# FDDplus3.net
KiCad netlist of a schematic drawn in Altium Designer
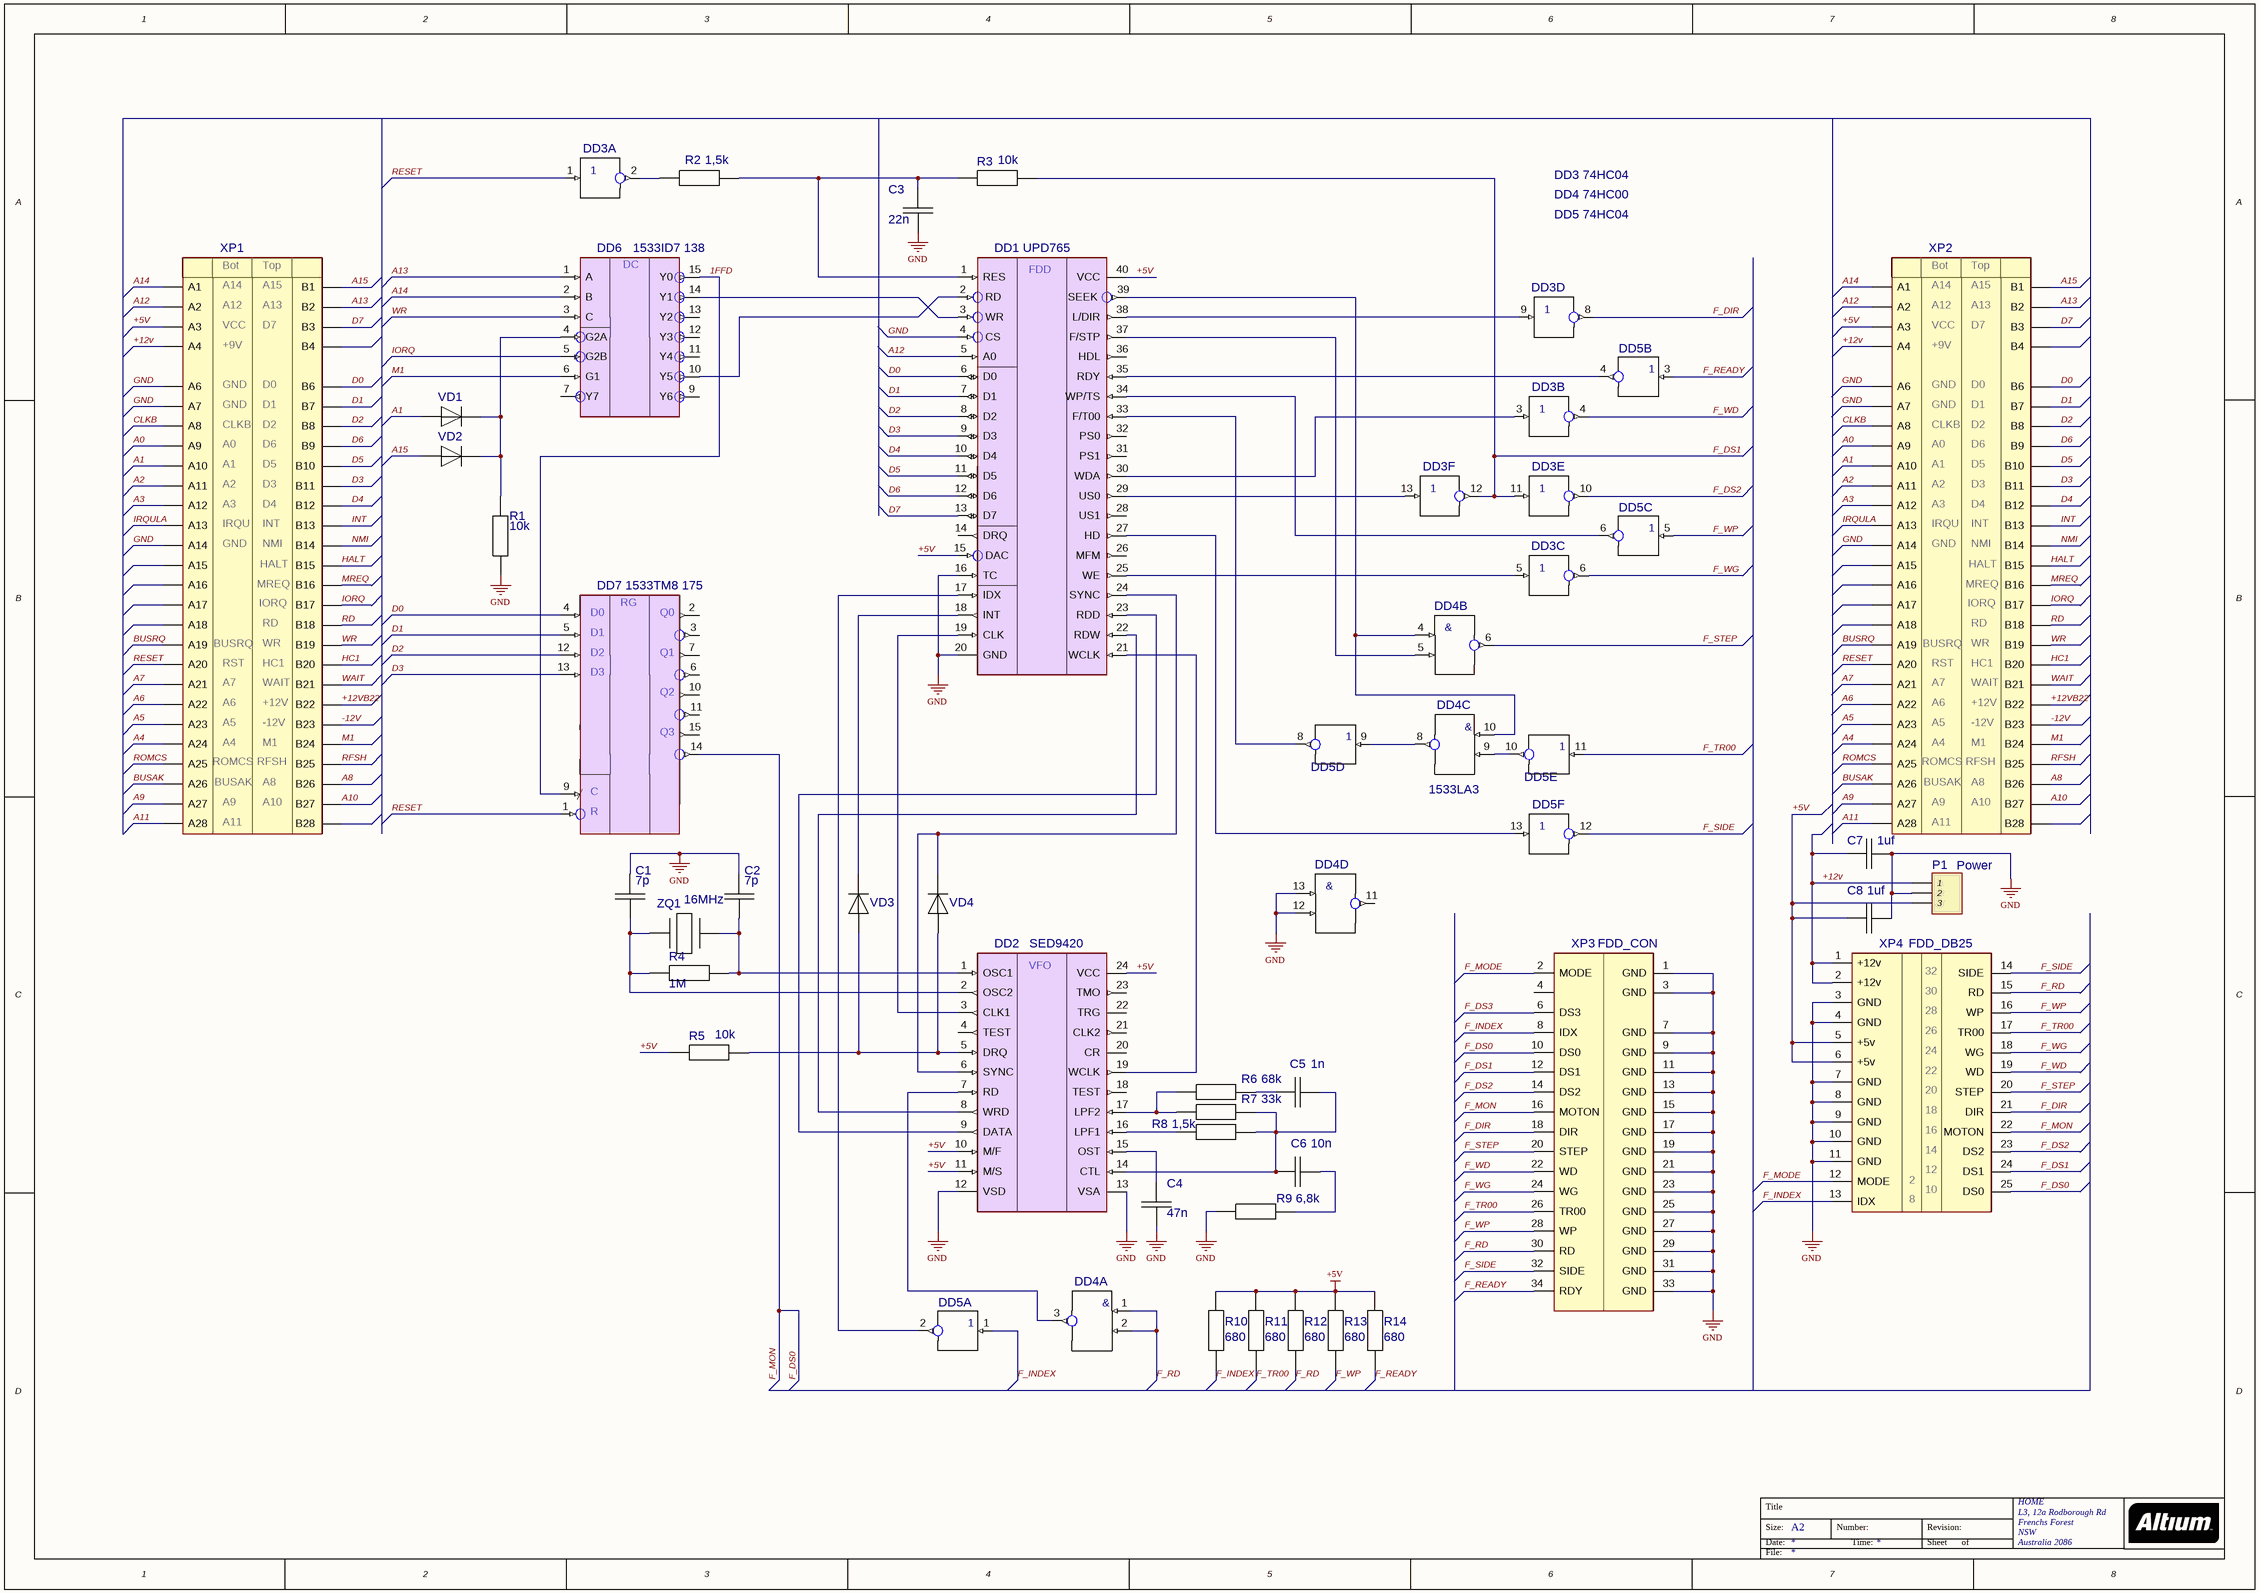
[diagram p0: FDDplus3.SchDoc]

(export (version "E")
  (design (tool "Eeschema 10.0.6"))
  (components
    (comp (ref "C1")
      (value "7p")
      (footprint "K10-17_75")
      (fields (field (name "Comment") "K10-17_75"))
      (libsource (lib "Pentagon") (part "K10-17_75"))
    )
    (comp (ref "C2")
      (value "7p")
      (footprint "K10-17_75")
      (fields (field (name "Comment") "K10-17_75"))
      (libsource (lib "Pentagon") (part "K10-17_75"))
    )
    (comp (ref "C3")
      (value "22n")
      (footprint "K10-17_75")
      (fields (field (name "Comment") "K10-17_75"))
      (libsource (lib "Pentagon") (part "K10-17_75"))
    )
    (comp (ref "C4")
      (value "47n")
      (footprint "K10-17_75")
      (fields (field (name "Comment") "K10-17_75"))
      (libsource (lib "Pentagon") (part "K10-17_75"))
    )
    (comp (ref "C5")
      (value "1n")
      (footprint "K10-17_75")
      (fields (field (name "Comment") "K10-17_75"))
      (libsource (lib "Pentagon") (part "K10-17_75"))
    )
    (comp (ref "C6")
      (value "10n")
      (footprint "K10-17_75")
      (fields (field (name "Comment") "K10-17_75"))
      (libsource (lib "Pentagon") (part "K10-17_75"))
    )
    (comp (ref "C7")
      (value "1uf")
      (footprint "K10-17_75")
      (fields (field (name "Comment") "K10-17_75"))
      (libsource (lib "Pentagon") (part "K10-17_75"))
    )
    (comp (ref "C8")
      (value "1uf")
      (footprint "K10-17_75")
      (fields (field (name "Comment") "K10-17_75"))
      (libsource (lib "Pentagon") (part "K10-17_75"))
    )
    (comp (ref "DD1") (value "UPD765") (footprint "DIP40_15") (libsource (lib "Pentagon") (part "UPD765")))
    (comp (ref "DD2") (value "SED9420") (footprint "DIP24_15") (libsource (lib "Pentagon") (part "SED9420")))
    (comp (ref "DD3") (value "1533LN1") (footprint "DIP14") (libsource (lib "") (part "1533LN1_2")))
    (comp (ref "DD4") (value "1533LA3") (footprint "DIP14") (libsource (lib "Pentagon") (part "1533LA3")))
    (comp (ref "DD5") (value "1533LN1") (footprint "DIP14") (libsource (lib "") (part "1533LN1_1")))
    (comp (ref "DD6") (value "1533ID7 138") (footprint "DIP16") (libsource (lib "Pentagon") (part "1533ID7")))
    (comp (ref "DD7") (value "1533TM8 175") (footprint "DIP16") (libsource (lib "Pentagon") (part "1533TM8")))
    (comp (ref "P1")
      (value "Power")
      (footprint "HDR1X3")
      (description "Header, 3-Pin")
      (fields (field (name "PUBLISHER") "Altium Limited"))
      (libsource (lib "Miscellaneous Connectors") (part "Header 3"))
    )
    (comp (ref "R1")
      (value "10k")
      (footprint "R0125-2_5")
      (fields (field (name "Comment") "R0125-2_5"))
      (libsource (lib "Pentagon") (part "R0125-2_5"))
    )
    (comp (ref "R2")
      (value "1,5k")
      (footprint "R0125-2_5")
      (fields (field (name "Comment") "R0125-2_5"))
      (libsource (lib "Pentagon") (part "R0125-2_5"))
    )
    (comp (ref "R3")
      (value "10k")
      (footprint "R0125-2_5")
      (fields (field (name "Comment") "R0125-2_5"))
      (libsource (lib "Pentagon") (part "R0125-2_5"))
    )
    (comp (ref "R4")
      (value "1M")
      (footprint "R0125-2_5")
      (fields (field (name "Comment") "R0125-2_5"))
      (libsource (lib "Pentagon") (part "R0125-2_5"))
    )
    (comp (ref "R5")
      (value "10k")
      (footprint "R0125-2_5")
      (fields (field (name "Comment") "R0125-2_5"))
      (libsource (lib "Pentagon") (part "R0125-2_5"))
    )
    (comp (ref "R6")
      (value "68k")
      (footprint "R0125-2_5")
      (fields (field (name "Comment") "R0125-2_5"))
      (libsource (lib "Pentagon") (part "R0125-2_5"))
    )
    (comp (ref "R7")
      (value "33k")
      (footprint "R0125-2_5")
      (fields (field (name "Comment") "R0125-2_5"))
      (libsource (lib "Pentagon") (part "R0125-2_5"))
    )
    (comp (ref "R8")
      (value "1,5k")
      (footprint "R0125-2_5")
      (fields (field (name "Comment") "R0125-2_5"))
      (libsource (lib "Pentagon") (part "R0125-2_5"))
    )
    (comp (ref "R9")
      (value "6,8k")
      (footprint "R0125-2_5")
      (fields (field (name "Comment") "R0125-2_5"))
      (libsource (lib "Pentagon") (part "R0125-2_5"))
    )
    (comp (ref "R10")
      (value "680")
      (footprint "R0125-2_5")
      (fields (field (name "Comment") "R0125-2_5"))
      (libsource (lib "Pentagon") (part "R0125-2_5"))
    )
    (comp (ref "R11")
      (value "680")
      (footprint "R0125-2_5")
      (fields (field (name "Comment") "R0125-2_5"))
      (libsource (lib "Pentagon") (part "R0125-2_5"))
    )
    (comp (ref "R12")
      (value "680")
      (footprint "R0125-2_5")
      (fields (field (name "Comment") "R0125-2_5"))
      (libsource (lib "Pentagon") (part "R0125-2_5"))
    )
    (comp (ref "R13")
      (value "680")
      (footprint "R0125-2_5")
      (fields (field (name "Comment") "R0125-2_5"))
      (libsource (lib "Pentagon") (part "R0125-2_5"))
    )
    (comp (ref "R14")
      (value "680")
      (footprint "R0125-2_5")
      (fields (field (name "Comment") "R0125-2_5"))
      (libsource (lib "Pentagon") (part "R0125-2_5"))
    )
    (comp (ref "VD1")
      (value "KD522-2_5")
      (footprint "KD522-2_5")
      (libsource (lib "Pentagon") (part "KD522-2_5"))
    )
    (comp (ref "VD2")
      (value "KD522-2_5")
      (footprint "KD522-2_5")
      (libsource (lib "Pentagon") (part "KD522-2_5"))
    )
    (comp (ref "VD3")
      (value "KD522-2_5")
      (footprint "KD522-2_5")
      (libsource (lib "Pentagon") (part "KD522-2_5"))
    )
    (comp (ref "VD4")
      (value "KD522-2_5")
      (footprint "KD522-2_5")
      (libsource (lib "Pentagon") (part "KD522-2_5"))
    )
    (comp (ref "XP1") (value "ZX EDGE") (footprint "ZX_EDGE") (libsource (lib "Pentagon") (part "ZX EDGE")))
    (comp (ref "XP2") (value "ZX EDGE") (footprint "ZX_EDGE") (libsource (lib "Pentagon") (part "ZX EDGE")))
    (comp (ref "XP3")
      (value "FDD_CON")
      (footprint "FDD_CON_Male")
      (libsource (lib "Pentagon") (part "FDD_CON"))
    )
    (comp (ref "XP4")
      (value "FDD_DB25")
      (footprint "DSUB1.385-2H25A")
      (libsource (lib "Pentagon") (part "FDD_DB25"))
    )
    (comp (ref "ZQ1")
      (value "16MHz")
      (footprint "RK169MD")
      (fields (field (name "Comment") "RK169MD"))
      (libsource (lib "Pentagon") (part "RK169MD"))
    )
  )
  (nets
    (net (code "1") (name "+5V") (class "Default")
      (node (ref "C8") (pin "2") (pinfunction "B_2") (pintype "passive"))
      (node (ref "DD1") (pin "15") (pinfunction "DAC_15") (pintype "input"))
      (node (ref "DD1") (pin "40") (pinfunction "VCC_40") (pintype "power_in"))
      (node (ref "DD2") (pin "10") (pinfunction "M/F_10") (pintype "input"))
      (node (ref "DD2") (pin "11") (pinfunction "M/S_11") (pintype "input"))
      (node (ref "DD2") (pin "24") (pinfunction "VCC_24") (pintype "power_in"))
      (node (ref "DD3") (pin "14") (pinfunction "+5V_14") (pintype "power_in"))
      (node (ref "DD4") (pin "14") (pinfunction "+5V_14") (pintype "power_in"))
      (node (ref "DD5") (pin "14") (pinfunction "+5V_14") (pintype "power_in"))
      (node (ref "DD6") (pin "16") (pinfunction "+5V_16") (pintype "power_in"))
      (node (ref "DD7") (pin "16") (pinfunction "+5V_16") (pintype "power_in"))
      (node (ref "P1") (pin "3") (pinfunction "3_3") (pintype "passive"))
      (node (ref "R10") (pin "1") (pinfunction "A_1") (pintype "passive"))
      (node (ref "R11") (pin "1") (pinfunction "A_1") (pintype "passive"))
      (node (ref "R12") (pin "1") (pinfunction "A_1") (pintype "passive"))
      (node (ref "R13") (pin "1") (pinfunction "A_1") (pintype "passive"))
      (node (ref "R14") (pin "1") (pinfunction "A_1") (pintype "passive"))
      (node (ref "R5") (pin "2") (pinfunction "B_2") (pintype "passive"))
      (node (ref "XP1") (pin "3") (pinfunction "A3_3") (pintype "power_in"))
      (node (ref "XP2") (pin "3") (pinfunction "A3_3") (pintype "power_in"))
      (node (ref "XP4") (pin "5") (pinfunction "+5v_5") (pintype "passive"))
      (node (ref "XP4") (pin "6") (pinfunction "+5v_6") (pintype "passive"))
    )
    (net (code "2") (name "/+12VB22") (class "Default")
      (node (ref "XP1") (pin "50") (pinfunction "B22_50") (pintype "passive"))
      (node (ref "XP2") (pin "50") (pinfunction "B22_50") (pintype "passive"))
    )
    (net (code "3") (name "/+12v") (class "Default")
      (node (ref "C7") (pin "2") (pinfunction "B_2") (pintype "passive"))
      (node (ref "P1") (pin "1") (pinfunction "1_1") (pintype "passive"))
      (node (ref "XP1") (pin "4") (pinfunction "A4_4") (pintype "passive"))
      (node (ref "XP2") (pin "4") (pinfunction "A4_4") (pintype "passive"))
      (node (ref "XP4") (pin "1") (pinfunction "+12v_1") (pintype "passive"))
      (node (ref "XP4") (pin "2") (pinfunction "+12v_2") (pintype "passive"))
    )
    (net (code "4") (name "/-12V") (class "Default")
      (node (ref "XP1") (pin "51") (pinfunction "B23_51") (pintype "passive"))
      (node (ref "XP2") (pin "51") (pinfunction "B23_51") (pintype "passive"))
    )
    (net (code "5") (name "/1FFD") (class "Default")
      (node (ref "DD6") (pin "15") (pinfunction "Y0_15") (pintype "output"))
      (node (ref "DD7") (pin "9") (pinfunction "C_9") (pintype "input"))
    )
    (net (code "6") (name "/A0") (class "Default")
      (node (ref "XP1") (pin "9") (pinfunction "A9_9") (pintype "passive"))
      (node (ref "XP2") (pin "9") (pinfunction "A9_9") (pintype "passive"))
    )
    (net (code "7") (name "/A1") (class "Default")
      (node (ref "VD1") (pin "1") (pinfunction "A_1") (pintype "passive"))
      (node (ref "XP1") (pin "10") (pinfunction "A10_10") (pintype "passive"))
      (node (ref "XP2") (pin "10") (pinfunction "A10_10") (pintype "passive"))
    )
    (net (code "8") (name "/A2") (class "Default")
      (node (ref "XP1") (pin "11") (pinfunction "A11_11") (pintype "passive"))
      (node (ref "XP2") (pin "11") (pinfunction "A11_11") (pintype "passive"))
    )
    (net (code "9") (name "/A3") (class "Default")
      (node (ref "XP1") (pin "12") (pinfunction "A12_12") (pintype "passive"))
      (node (ref "XP2") (pin "12") (pinfunction "A12_12") (pintype "passive"))
    )
    (net (code "10") (name "/A4") (class "Default")
      (node (ref "XP1") (pin "24") (pinfunction "A24_24") (pintype "passive"))
      (node (ref "XP2") (pin "24") (pinfunction "A24_24") (pintype "passive"))
    )
    (net (code "11") (name "/A5") (class "Default")
      (node (ref "XP1") (pin "23") (pinfunction "A23_23") (pintype "passive"))
      (node (ref "XP2") (pin "23") (pinfunction "A23_23") (pintype "passive"))
    )
    (net (code "12") (name "/A6") (class "Default")
      (node (ref "XP1") (pin "22") (pinfunction "A22_22") (pintype "passive"))
      (node (ref "XP2") (pin "22") (pinfunction "A22_22") (pintype "passive"))
    )
    (net (code "13") (name "/A7") (class "Default")
      (node (ref "XP1") (pin "21") (pinfunction "A21_21") (pintype "passive"))
      (node (ref "XP2") (pin "21") (pinfunction "A21_21") (pintype "passive"))
    )
    (net (code "14") (name "/A8") (class "Default")
      (node (ref "XP1") (pin "54") (pinfunction "B26_54") (pintype "passive"))
      (node (ref "XP2") (pin "54") (pinfunction "B26_54") (pintype "passive"))
    )
    (net (code "15") (name "/A9") (class "Default")
      (node (ref "XP1") (pin "27") (pinfunction "A27_27") (pintype "passive"))
      (node (ref "XP2") (pin "27") (pinfunction "A27_27") (pintype "passive"))
    )
    (net (code "16") (name "/A10") (class "Default")
      (node (ref "XP1") (pin "55") (pinfunction "B27_55") (pintype "passive"))
      (node (ref "XP2") (pin "55") (pinfunction "B27_55") (pintype "passive"))
    )
    (net (code "17") (name "/A11") (class "Default")
      (node (ref "XP1") (pin "28") (pinfunction "A28_28") (pintype "passive"))
      (node (ref "XP2") (pin "28") (pinfunction "A28_28") (pintype "passive"))
    )
    (net (code "18") (name "/A12") (class "Default")
      (node (ref "DD1") (pin "5") (pinfunction "A0_5") (pintype "input"))
      (node (ref "XP1") (pin "2") (pinfunction "A2_2") (pintype "passive"))
      (node (ref "XP2") (pin "2") (pinfunction "A2_2") (pintype "passive"))
    )
    (net (code "19") (name "/A13") (class "Default")
      (node (ref "DD6") (pin "1") (pinfunction "A_1") (pintype "input"))
      (node (ref "XP1") (pin "30") (pinfunction "B2_30") (pintype "passive"))
      (node (ref "XP2") (pin "30") (pinfunction "B2_30") (pintype "passive"))
    )
    (net (code "20") (name "/A14") (class "Default")
      (node (ref "DD6") (pin "2") (pinfunction "B_2") (pintype "input"))
      (node (ref "XP1") (pin "1") (pinfunction "A1_1") (pintype "passive"))
      (node (ref "XP2") (pin "1") (pinfunction "A1_1") (pintype "passive"))
    )
    (net (code "21") (name "/A15") (class "Default")
      (node (ref "VD2") (pin "1") (pinfunction "A_1") (pintype "passive"))
      (node (ref "XP1") (pin "29") (pinfunction "B1_29") (pintype "passive"))
      (node (ref "XP2") (pin "29") (pinfunction "B1_29") (pintype "passive"))
    )
    (net (code "22") (name "/BUSAK") (class "Default")
      (node (ref "XP1") (pin "26") (pinfunction "A26_26") (pintype "passive"))
      (node (ref "XP2") (pin "26") (pinfunction "A26_26") (pintype "passive"))
    )
    (net (code "23") (name "/BUSRQ") (class "Default")
      (node (ref "XP1") (pin "19") (pinfunction "A19_19") (pintype "passive"))
      (node (ref "XP2") (pin "19") (pinfunction "A19_19") (pintype "passive"))
    )
    (net (code "24") (name "/CLKB") (class "Default")
      (node (ref "XP1") (pin "8") (pinfunction "A8_8") (pintype "passive"))
      (node (ref "XP2") (pin "8") (pinfunction "A8_8") (pintype "passive"))
    )
    (net (code "25") (name "/D0") (class "Default")
      (node (ref "DD1") (pin "6") (pinfunction "D0_6") (pintype "bidirectional"))
      (node (ref "DD7") (pin "4") (pinfunction "D0_4") (pintype "input"))
      (node (ref "XP1") (pin "34") (pinfunction "B6_34") (pintype "passive"))
      (node (ref "XP2") (pin "34") (pinfunction "B6_34") (pintype "passive"))
    )
    (net (code "26") (name "/D1") (class "Default")
      (node (ref "DD1") (pin "7") (pinfunction "D1_7") (pintype "bidirectional"))
      (node (ref "DD7") (pin "5") (pinfunction "D1_5") (pintype "input"))
      (node (ref "XP1") (pin "35") (pinfunction "B7_35") (pintype "passive"))
      (node (ref "XP2") (pin "35") (pinfunction "B7_35") (pintype "passive"))
    )
    (net (code "27") (name "/D2") (class "Default")
      (node (ref "DD1") (pin "8") (pinfunction "D2_8") (pintype "bidirectional"))
      (node (ref "DD7") (pin "12") (pinfunction "D2_12") (pintype "input"))
      (node (ref "XP1") (pin "36") (pinfunction "B8_36") (pintype "passive"))
      (node (ref "XP2") (pin "36") (pinfunction "B8_36") (pintype "passive"))
    )
    (net (code "28") (name "/D3") (class "Default")
      (node (ref "DD1") (pin "9") (pinfunction "D3_9") (pintype "bidirectional"))
      (node (ref "DD7") (pin "13") (pinfunction "D3_13") (pintype "input"))
      (node (ref "XP1") (pin "39") (pinfunction "B11_39") (pintype "passive"))
      (node (ref "XP2") (pin "39") (pinfunction "B11_39") (pintype "passive"))
    )
    (net (code "29") (name "/D4") (class "Default")
      (node (ref "DD1") (pin "10") (pinfunction "D4_10") (pintype "bidirectional"))
      (node (ref "XP1") (pin "40") (pinfunction "B12_40") (pintype "passive"))
      (node (ref "XP2") (pin "40") (pinfunction "B12_40") (pintype "passive"))
    )
    (net (code "30") (name "/D5") (class "Default")
      (node (ref "DD1") (pin "11") (pinfunction "D5_11") (pintype "bidirectional"))
      (node (ref "XP1") (pin "38") (pinfunction "B10_38") (pintype "passive"))
      (node (ref "XP2") (pin "38") (pinfunction "B10_38") (pintype "passive"))
    )
    (net (code "31") (name "/D6") (class "Default")
      (node (ref "DD1") (pin "12") (pinfunction "D6_12") (pintype "bidirectional"))
      (node (ref "XP1") (pin "37") (pinfunction "B9_37") (pintype "passive"))
      (node (ref "XP2") (pin "37") (pinfunction "B9_37") (pintype "passive"))
    )
    (net (code "32") (name "/D7") (class "Default")
      (node (ref "DD1") (pin "13") (pinfunction "D7_13") (pintype "bidirectional"))
      (node (ref "XP1") (pin "31") (pinfunction "B3_31") (pintype "passive"))
      (node (ref "XP2") (pin "31") (pinfunction "B3_31") (pintype "passive"))
    )
    (net (code "33") (name "/F_DIR") (class "Default")
      (node (ref "DD3") (pin "8") (pinfunction "B_8") (pintype "output"))
      (node (ref "XP3") (pin "18") (pinfunction "DIR_18") (pintype "passive"))
      (node (ref "XP4") (pin "21") (pinfunction "DIR_21") (pintype "passive"))
    )
    (net (code "34") (name "/F_DS0") (class "Default")
      (node (ref "DD7") (pin "14") (pinfunction "Q4/_14") (pintype "output"))
      (node (ref "XP3") (pin "10") (pinfunction "DS0_10") (pintype "passive"))
      (node (ref "XP3") (pin "16") (pinfunction "MOTON_16") (pintype "passive"))
      (node (ref "XP4") (pin "22") (pinfunction "MOTON_22") (pintype "passive"))
      (node (ref "XP4") (pin "25") (pinfunction "DS0_25") (pintype "passive"))
    )
    (net (code "35") (name "/F_DS1") (class "Default")
      (node (ref "DD3") (pin "11") (pinfunction "A_11") (pintype "input"))
      (node (ref "DD3") (pin "12") (pinfunction "B_12") (pintype "output"))
      (node (ref "R3") (pin "1") (pinfunction "A_1") (pintype "passive"))
      (node (ref "XP3") (pin "12") (pinfunction "DS1_12") (pintype "passive"))
      (node (ref "XP4") (pin "24") (pinfunction "DS1_24") (pintype "passive"))
    )
    (net (code "36") (name "/F_DS2") (class "Default")
      (node (ref "DD3") (pin "10") (pinfunction "B_10") (pintype "output"))
      (node (ref "XP3") (pin "14") (pinfunction "DS2_14") (pintype "passive"))
      (node (ref "XP4") (pin "23") (pinfunction "DS2_23") (pintype "passive"))
    )
    (net (code "37") (name "/F_DS3") (class "Default")
      (node (ref "XP3") (pin "6") (pinfunction "DS3_6") (pintype "passive"))
    )
    (net (code "38") (name "/F_INDEX") (class "Default")
      (node (ref "DD5") (pin "1") (pinfunction "A_1") (pintype "input"))
      (node (ref "R10") (pin "2") (pinfunction "B_2") (pintype "passive"))
      (node (ref "XP3") (pin "8") (pinfunction "IDX_8") (pintype "passive"))
      (node (ref "XP4") (pin "13") (pinfunction "IDX_13") (pintype "passive"))
    )
    (net (code "39") (name "/F_MODE") (class "Default")
      (node (ref "XP3") (pin "2") (pinfunction "MODE_2") (pintype "passive"))
      (node (ref "XP4") (pin "12") (pinfunction "MODE_12") (pintype "passive"))
    )
    (net (code "40") (name "/F_RD") (class "Default")
      (node (ref "DD4") (pin "1") (pinfunction "A_1") (pintype "input"))
      (node (ref "DD4") (pin "2") (pinfunction "B_2") (pintype "input"))
      (node (ref "R12") (pin "2") (pinfunction "B_2") (pintype "passive"))
      (node (ref "XP3") (pin "30") (pinfunction "RD_30") (pintype "passive"))
      (node (ref "XP4") (pin "15") (pinfunction "RD_15") (pintype "passive"))
    )
    (net (code "41") (name "/F_READY") (class "Default")
      (node (ref "DD5") (pin "3") (pinfunction "A_3") (pintype "input"))
      (node (ref "R14") (pin "2") (pinfunction "B_2") (pintype "passive"))
      (node (ref "XP3") (pin "34") (pinfunction "RDY_34") (pintype "passive"))
    )
    (net (code "42") (name "/F_SIDE") (class "Default")
      (node (ref "DD5") (pin "12") (pinfunction "B_12") (pintype "output"))
      (node (ref "XP3") (pin "32") (pinfunction "SIDE_32") (pintype "passive"))
      (node (ref "XP4") (pin "14") (pinfunction "SIDE_14") (pintype "passive"))
    )
    (net (code "43") (name "/F_STEP") (class "Default")
      (node (ref "DD4") (pin "6") (pinfunction "C_6") (pintype "output"))
      (node (ref "XP3") (pin "20") (pinfunction "STEP_20") (pintype "passive"))
      (node (ref "XP4") (pin "20") (pinfunction "STEP_20") (pintype "passive"))
    )
    (net (code "44") (name "/F_TR00") (class "Default")
      (node (ref "DD5") (pin "11") (pinfunction "A_11") (pintype "input"))
      (node (ref "R11") (pin "2") (pinfunction "B_2") (pintype "passive"))
      (node (ref "XP3") (pin "26") (pinfunction "TR00_26") (pintype "passive"))
      (node (ref "XP4") (pin "17") (pinfunction "TR00_17") (pintype "passive"))
    )
    (net (code "45") (name "/F_WD") (class "Default")
      (node (ref "DD3") (pin "4") (pinfunction "B_4") (pintype "output"))
      (node (ref "XP3") (pin "22") (pinfunction "WD_22") (pintype "passive"))
      (node (ref "XP4") (pin "19") (pinfunction "WD_19") (pintype "passive"))
    )
    (net (code "46") (name "/F_WG") (class "Default")
      (node (ref "DD3") (pin "6") (pinfunction "B_6") (pintype "output"))
      (node (ref "XP3") (pin "24") (pinfunction "WG_24") (pintype "passive"))
      (node (ref "XP4") (pin "18") (pinfunction "WG_18") (pintype "passive"))
    )
    (net (code "47") (name "/F_WP") (class "Default")
      (node (ref "DD5") (pin "5") (pinfunction "A_5") (pintype "input"))
      (node (ref "R13") (pin "2") (pinfunction "B_2") (pintype "passive"))
      (node (ref "XP3") (pin "28") (pinfunction "WP_28") (pintype "passive"))
      (node (ref "XP4") (pin "16") (pinfunction "WP_16") (pintype "passive"))
    )
    (net (code "48") (name "/HALT") (class "Default")
      (node (ref "XP1") (pin "43") (pinfunction "B15_43") (pintype "passive"))
      (node (ref "XP2") (pin "43") (pinfunction "B15_43") (pintype "passive"))
    )
    (net (code "49") (name "/HC1") (class "Default")
      (node (ref "XP1") (pin "48") (pinfunction "B20_48") (pintype "passive"))
      (node (ref "XP2") (pin "48") (pinfunction "B20_48") (pintype "passive"))
    )
    (net (code "50") (name "/INT") (class "Default")
      (node (ref "XP1") (pin "41") (pinfunction "B13_41") (pintype "passive"))
      (node (ref "XP2") (pin "41") (pinfunction "B13_41") (pintype "passive"))
    )
    (net (code "51") (name "/IORQ") (class "Default")
      (node (ref "DD6") (pin "5") (pinfunction "G2B_5") (pintype "input"))
      (node (ref "XP1") (pin "45") (pinfunction "B17_45") (pintype "passive"))
      (node (ref "XP2") (pin "45") (pinfunction "B17_45") (pintype "passive"))
    )
    (net (code "52") (name "/IRQULA") (class "Default")
      (node (ref "XP1") (pin "13") (pinfunction "A13_13") (pintype "passive"))
      (node (ref "XP2") (pin "13") (pinfunction "A13_13") (pintype "passive"))
    )
    (net (code "53") (name "/M1") (class "Default")
      (node (ref "DD6") (pin "6") (pinfunction "G1_6") (pintype "input"))
      (node (ref "XP1") (pin "52") (pinfunction "B24_52") (pintype "passive"))
      (node (ref "XP2") (pin "52") (pinfunction "B24_52") (pintype "passive"))
    )
    (net (code "54") (name "/MREQ") (class "Default")
      (node (ref "XP1") (pin "44") (pinfunction "B16_44") (pintype "passive"))
      (node (ref "XP2") (pin "44") (pinfunction "B16_44") (pintype "passive"))
    )
    (net (code "55") (name "/NMI") (class "Default")
      (node (ref "XP1") (pin "42") (pinfunction "B14_42") (pintype "passive"))
      (node (ref "XP2") (pin "42") (pinfunction "B14_42") (pintype "passive"))
    )
    (net (code "56") (name "/RD") (class "Default")
      (node (ref "XP1") (pin "46") (pinfunction "B18_46") (pintype "passive"))
      (node (ref "XP2") (pin "46") (pinfunction "B18_46") (pintype "passive"))
    )
    (net (code "57") (name "/RESET") (class "Default")
      (node (ref "DD3") (pin "1") (pinfunction "A_1") (pintype "input"))
      (node (ref "DD7") (pin "1") (pinfunction "R_1") (pintype "input"))
      (node (ref "XP1") (pin "20") (pinfunction "A20_20") (pintype "passive"))
      (node (ref "XP2") (pin "20") (pinfunction "A20_20") (pintype "passive"))
    )
    (net (code "58") (name "/RFSH") (class "Default")
      (node (ref "XP1") (pin "53") (pinfunction "B25_53") (pintype "passive"))
      (node (ref "XP2") (pin "53") (pinfunction "B25_53") (pintype "passive"))
    )
    (net (code "59") (name "/ROMCS") (class "Default")
      (node (ref "XP1") (pin "25") (pinfunction "A25_25") (pintype "passive"))
      (node (ref "XP2") (pin "25") (pinfunction "A25_25") (pintype "passive"))
    )
    (net (code "60") (name "/WAIT") (class "Default")
      (node (ref "XP1") (pin "49") (pinfunction "B21_49") (pintype "passive"))
      (node (ref "XP2") (pin "49") (pinfunction "B21_49") (pintype "passive"))
    )
    (net (code "61") (name "/WR") (class "Default")
      (node (ref "DD6") (pin "3") (pinfunction "C_3") (pintype "input"))
      (node (ref "XP1") (pin "47") (pinfunction "B19_47") (pintype "passive"))
      (node (ref "XP2") (pin "47") (pinfunction "B19_47") (pintype "passive"))
    )
    (net (code "62") (name "GND") (class "Default")
      (node (ref "C1") (pin "2") (pinfunction "B_2") (pintype "passive"))
      (node (ref "C2") (pin "2") (pinfunction "B_2") (pintype "passive"))
      (node (ref "C3") (pin "1") (pinfunction "A_1") (pintype "passive"))
      (node (ref "C4") (pin "1") (pinfunction "A_1") (pintype "passive"))
      (node (ref "C7") (pin "1") (pinfunction "A_1") (pintype "passive"))
      (node (ref "C8") (pin "1") (pinfunction "A_1") (pintype "passive"))
      (node (ref "DD1") (pin "16") (pinfunction "TC_16") (pintype "input"))
      (node (ref "DD1") (pin "20") (pinfunction "GND_20") (pintype "power_in"))
      (node (ref "DD1") (pin "4") (pinfunction "CS_4") (pintype "input"))
      (node (ref "DD2") (pin "12") (pinfunction "VSD_12") (pintype "power_in"))
      (node (ref "DD2") (pin "13") (pinfunction "VSA_13") (pintype "power_in"))
      (node (ref "DD3") (pin "7") (pinfunction "GND_7") (pintype "power_in"))
      (node (ref "DD4") (pin "12") (pinfunction "B_12") (pintype "input"))
      (node (ref "DD4") (pin "13") (pinfunction "A_13") (pintype "input"))
      (node (ref "DD4") (pin "7") (pinfunction "GND_7") (pintype "power_in"))
      (node (ref "DD5") (pin "7") (pinfunction "GND_7") (pintype "power_in"))
      (node (ref "DD6") (pin "8") (pinfunction "GND_8") (pintype "power_in"))
      (node (ref "DD7") (pin "8") (pinfunction "GND_8") (pintype "power_in"))
      (node (ref "P1") (pin "2") (pinfunction "2_2") (pintype "passive"))
      (node (ref "R1") (pin "1") (pinfunction "A_1") (pintype "passive"))
      (node (ref "R9") (pin "2") (pinfunction "B_2") (pintype "passive"))
      (node (ref "XP1") (pin "14") (pinfunction "A14_14") (pintype "power_in"))
      (node (ref "XP1") (pin "6") (pinfunction "A6_6") (pintype "power_in"))
      (node (ref "XP1") (pin "7") (pinfunction "A7_7") (pintype "power_in"))
      (node (ref "XP2") (pin "14") (pinfunction "A14_14") (pintype "power_in"))
      (node (ref "XP2") (pin "6") (pinfunction "A6_6") (pintype "power_in"))
      (node (ref "XP2") (pin "7") (pinfunction "A7_7") (pintype "power_in"))
      (node (ref "XP3") (pin "1") (pinfunction "GND_1") (pintype "passive"))
      (node (ref "XP3") (pin "11") (pinfunction "GND_11") (pintype "passive"))
      (node (ref "XP3") (pin "13") (pinfunction "GND_13") (pintype "passive"))
      (node (ref "XP3") (pin "15") (pinfunction "GND_15") (pintype "passive"))
      (node (ref "XP3") (pin "17") (pinfunction "GND_17") (pintype "passive"))
      (node (ref "XP3") (pin "19") (pinfunction "GND_19") (pintype "passive"))
      (node (ref "XP3") (pin "21") (pinfunction "GND_21") (pintype "passive"))
      (node (ref "XP3") (pin "23") (pinfunction "GND_23") (pintype "passive"))
      (node (ref "XP3") (pin "25") (pinfunction "GND_25") (pintype "passive"))
      (node (ref "XP3") (pin "27") (pinfunction "GND_27") (pintype "passive"))
      (node (ref "XP3") (pin "29") (pinfunction "GND_29") (pintype "passive"))
      (node (ref "XP3") (pin "3") (pinfunction "GND_3") (pintype "passive"))
      (node (ref "XP3") (pin "31") (pinfunction "GND_31") (pintype "passive"))
      (node (ref "XP3") (pin "33") (pinfunction "GND_33") (pintype "passive"))
      (node (ref "XP3") (pin "7") (pinfunction "GND_7") (pintype "passive"))
      (node (ref "XP3") (pin "9") (pinfunction "GND_9") (pintype "passive"))
      (node (ref "XP4") (pin "10") (pinfunction "GND_10") (pintype "passive"))
      (node (ref "XP4") (pin "11") (pinfunction "GND_11") (pintype "passive"))
      (node (ref "XP4") (pin "3") (pinfunction "GND_3") (pintype "passive"))
      (node (ref "XP4") (pin "4") (pinfunction "GND_4") (pintype "passive"))
      (node (ref "XP4") (pin "7") (pinfunction "GND_7") (pintype "passive"))
      (node (ref "XP4") (pin "8") (pinfunction "GND_8") (pintype "passive"))
      (node (ref "XP4") (pin "9") (pinfunction "GND_9") (pintype "passive"))
    )
    (net (code "63") (name "Net-(C1-A)") (class "Default")
      (node (ref "C1") (pin "1") (pinfunction "A_1") (pintype "passive"))
      (node (ref "DD2") (pin "2") (pinfunction "OSC2_2") (pintype "output"))
      (node (ref "R4") (pin "2") (pinfunction "B_2") (pintype "passive"))
      (node (ref "ZQ1") (pin "1") (pinfunction "A_1") (pintype "passive"))
    )
    (net (code "64") (name "Net-(C2-A)") (class "Default")
      (node (ref "C2") (pin "1") (pinfunction "A_1") (pintype "passive"))
      (node (ref "DD2") (pin "1") (pinfunction "OSC1_1") (pintype "input"))
      (node (ref "R4") (pin "1") (pinfunction "A_1") (pintype "passive"))
      (node (ref "ZQ1") (pin "2") (pinfunction "B_2") (pintype "passive"))
    )
    (net (code "65") (name "Net-(C3-B)") (class "Default")
      (node (ref "C3") (pin "2") (pinfunction "B_2") (pintype "passive"))
      (node (ref "DD1") (pin "1") (pinfunction "RES_1") (pintype "input"))
      (node (ref "R2") (pin "1") (pinfunction "A_1") (pintype "passive"))
      (node (ref "R3") (pin "2") (pinfunction "B_2") (pintype "passive"))
    )
    (net (code "66") (name "Net-(C4-B)") (class "Default")
      (node (ref "C4") (pin "2") (pinfunction "B_2") (pintype "passive"))
      (node (ref "DD2") (pin "15") (pinfunction "OST_15") (pintype "input"))
    )
    (net (code "67") (name "Net-(C5-A)") (class "Default")
      (node (ref "C5") (pin "1") (pinfunction "A_1") (pintype "passive"))
      (node (ref "C6") (pin "2") (pinfunction "B_2") (pintype "passive"))
      (node (ref "DD2") (pin "14") (pinfunction "CTL_14") (pintype "input"))
      (node (ref "R7") (pin "1") (pinfunction "A_1") (pintype "passive"))
      (node (ref "R8") (pin "1") (pinfunction "A_1") (pintype "passive"))
    )
    (net (code "68") (name "Net-(C5-B)") (class "Default")
      (node (ref "C5") (pin "2") (pinfunction "B_2") (pintype "passive"))
      (node (ref "R6") (pin "1") (pinfunction "A_1") (pintype "passive"))
    )
    (net (code "69") (name "Net-(C6-A)") (class "Default")
      (node (ref "C6") (pin "1") (pinfunction "A_1") (pintype "passive"))
      (node (ref "R9") (pin "1") (pinfunction "A_1") (pintype "passive"))
    )
    (net (code "70") (name "Net-(DD1-CLK)") (class "Default")
      (node (ref "DD1") (pin "19") (pinfunction "CLK_19") (pintype "input"))
      (node (ref "DD2") (pin "3") (pinfunction "CLK1_3") (pintype "output"))
    )
    (net (code "71") (name "Net-(DD1-F{slash}STP)") (class "Default")
      (node (ref "DD1") (pin "37") (pinfunction "F/STP_37") (pintype "output"))
      (node (ref "DD4") (pin "5") (pinfunction "B_5") (pintype "input"))
    )
    (net (code "72") (name "Net-(DD1-F{slash}T00)") (class "Default")
      (node (ref "DD1") (pin "33") (pinfunction "F/T00_33") (pintype "input"))
      (node (ref "DD5") (pin "8") (pinfunction "B_8") (pintype "output"))
    )
    (net (code "73") (name "Net-(DD1-HD)") (class "Default")
      (node (ref "DD1") (pin "27") (pinfunction "HD_27") (pintype "output"))
      (node (ref "DD5") (pin "13") (pinfunction "A_13") (pintype "input"))
    )
    (net (code "74") (name "Net-(DD1-IDX)") (class "Default")
      (node (ref "DD1") (pin "17") (pinfunction "IDX_17") (pintype "input"))
      (node (ref "DD5") (pin "2") (pinfunction "B_2") (pintype "output"))
    )
    (net (code "75") (name "Net-(DD1-INT)") (class "Default")
      (node (ref "DD1") (pin "18") (pinfunction "INT_18") (pintype "output"))
      (node (ref "VD3") (pin "2") (pinfunction "B_2") (pintype "passive"))
    )
    (net (code "76") (name "Net-(DD1-L{slash}DIR)") (class "Default")
      (node (ref "DD1") (pin "38") (pinfunction "L/DIR_38") (pintype "output"))
      (node (ref "DD3") (pin "9") (pinfunction "A_9") (pintype "input"))
    )
    (net (code "77") (name "Net-(DD1-RD)") (class "Default")
      (node (ref "DD1") (pin "2") (pinfunction "RD_2") (pintype "input"))
      (node (ref "DD6") (pin "10") (pinfunction "Y5_10") (pintype "output"))
    )
    (net (code "78") (name "Net-(DD1-RDD)") (class "Default")
      (node (ref "DD1") (pin "23") (pinfunction "RDD_23") (pintype "input"))
      (node (ref "DD2") (pin "9") (pinfunction "DATA_9") (pintype "output"))
    )
    (net (code "79") (name "Net-(DD1-RDW)") (class "Default")
      (node (ref "DD1") (pin "22") (pinfunction "RDW_22") (pintype "input"))
      (node (ref "DD2") (pin "8") (pinfunction "WRD_8") (pintype "output"))
    )
    (net (code "80") (name "Net-(DD1-RDY)") (class "Default")
      (node (ref "DD1") (pin "35") (pinfunction "RDY_35") (pintype "input"))
      (node (ref "DD5") (pin "4") (pinfunction "B_4") (pintype "output"))
    )
    (net (code "81") (name "Net-(DD1-SEEK)") (class "Default")
      (node (ref "DD1") (pin "39") (pinfunction "SEEK_39") (pintype "output"))
      (node (ref "DD4") (pin "10") (pinfunction "A_10") (pintype "input"))
      (node (ref "DD4") (pin "4") (pinfunction "A_4") (pintype "input"))
    )
    (net (code "82") (name "Net-(DD1-SYNC)") (class "Default")
      (node (ref "DD1") (pin "24") (pinfunction "SYNC_24") (pintype "output"))
      (node (ref "DD2") (pin "6") (pinfunction "SYNC_6") (pintype "input"))
      (node (ref "VD4") (pin "2") (pinfunction "B_2") (pintype "passive"))
    )
    (net (code "83") (name "Net-(DD1-US0)") (class "Default")
      (node (ref "DD1") (pin "29") (pinfunction "US0_29") (pintype "output"))
      (node (ref "DD3") (pin "13") (pinfunction "A_13") (pintype "input"))
    )
    (net (code "84") (name "Net-(DD1-WCLK)") (class "Default")
      (node (ref "DD1") (pin "21") (pinfunction "WCLK_21") (pintype "input"))
      (node (ref "DD2") (pin "19") (pinfunction "WCLK_19") (pintype "output"))
    )
    (net (code "85") (name "Net-(DD1-WDA)") (class "Default")
      (node (ref "DD1") (pin "30") (pinfunction "WDA_30") (pintype "output"))
      (node (ref "DD3") (pin "3") (pinfunction "A_3") (pintype "input"))
    )
    (net (code "86") (name "Net-(DD1-WE)") (class "Default")
      (node (ref "DD1") (pin "25") (pinfunction "WE_25") (pintype "output"))
      (node (ref "DD3") (pin "5") (pinfunction "A_5") (pintype "input"))
    )
    (net (code "87") (name "Net-(DD1-WP{slash}TS)") (class "Default")
      (node (ref "DD1") (pin "34") (pinfunction "WP/TS_34") (pintype "input"))
      (node (ref "DD5") (pin "6") (pinfunction "B_6") (pintype "output"))
    )
    (net (code "88") (name "Net-(DD1-WR)") (class "Default")
      (node (ref "DD1") (pin "3") (pinfunction "WR_3") (pintype "input"))
      (node (ref "DD6") (pin "14") (pinfunction "Y1_14") (pintype "output"))
    )
    (net (code "89") (name "Net-(DD2-DRQ)") (class "Default")
      (node (ref "DD2") (pin "5") (pinfunction "DRQ_5") (pintype "input"))
      (node (ref "R5") (pin "1") (pinfunction "A_1") (pintype "passive"))
      (node (ref "VD3") (pin "1") (pinfunction "A_1") (pintype "passive"))
      (node (ref "VD4") (pin "1") (pinfunction "A_1") (pintype "passive"))
    )
    (net (code "90") (name "Net-(DD2-LPF1)") (class "Default")
      (node (ref "DD2") (pin "16") (pinfunction "LPF1_16") (pintype "input"))
      (node (ref "R8") (pin "2") (pinfunction "B_2") (pintype "passive"))
    )
    (net (code "91") (name "Net-(DD2-LPF2)") (class "Default")
      (node (ref "DD2") (pin "17") (pinfunction "LPF2_17") (pintype "input"))
      (node (ref "R6") (pin "2") (pinfunction "B_2") (pintype "passive"))
      (node (ref "R7") (pin "2") (pinfunction "B_2") (pintype "passive"))
    )
    (net (code "92") (name "Net-(DD2-RD)") (class "Default")
      (node (ref "DD2") (pin "7") (pinfunction "RD_7") (pintype "input"))
      (node (ref "DD4") (pin "3") (pinfunction "C_3") (pintype "output"))
    )
    (net (code "93") (name "Net-(DD3A-B)") (class "Default")
      (node (ref "DD3") (pin "2") (pinfunction "B_2") (pintype "output"))
      (node (ref "R2") (pin "2") (pinfunction "B_2") (pintype "passive"))
    )
    (net (code "94") (name "Net-(DD4C-B)") (class "Default")
      (node (ref "DD4") (pin "9") (pinfunction "B_9") (pintype "input"))
      (node (ref "DD5") (pin "10") (pinfunction "B_10") (pintype "output"))
    )
    (net (code "95") (name "Net-(DD4C-C)") (class "Default")
      (node (ref "DD4") (pin "8") (pinfunction "C_8") (pintype "output"))
      (node (ref "DD5") (pin "9") (pinfunction "A_9") (pintype "input"))
    )
    (net (code "96") (name "Net-(DD6-G2A)") (class "Default")
      (node (ref "DD6") (pin "4") (pinfunction "G2A_4") (pintype "input"))
      (node (ref "R1") (pin "2") (pinfunction "B_2") (pintype "passive"))
      (node (ref "VD1") (pin "2") (pinfunction "B_2") (pintype "passive"))
      (node (ref "VD2") (pin "2") (pinfunction "B_2") (pintype "passive"))
    )
    (net (code "97") (name "unconnected-(DD1-DRQ-Pad14)") (class "Default")
      (node (ref "DD1") (pin "14") (pinfunction "DRQ_14") (pintype "output"))
    )
    (net (code "98") (name "unconnected-(DD1-HDL-Pad36)") (class "Default")
      (node (ref "DD1") (pin "36") (pinfunction "HDL_36") (pintype "output"))
    )
    (net (code "99") (name "unconnected-(DD1-MFM-Pad26)") (class "Default")
      (node (ref "DD1") (pin "26") (pinfunction "MFM_26") (pintype "output"))
    )
    (net (code "100") (name "unconnected-(DD1-PS0-Pad32)") (class "Default")
      (node (ref "DD1") (pin "32") (pinfunction "PS0_32") (pintype "output"))
    )
    (net (code "101") (name "unconnected-(DD1-PS1-Pad31)") (class "Default")
      (node (ref "DD1") (pin "31") (pinfunction "PS1_31") (pintype "output"))
    )
    (net (code "102") (name "unconnected-(DD1-US1-Pad28)") (class "Default")
      (node (ref "DD1") (pin "28") (pinfunction "US1_28") (pintype "output"))
    )
    (net (code "103") (name "unconnected-(DD2-CLK2-Pad21)") (class "Default")
      (node (ref "DD2") (pin "21") (pinfunction "CLK2_21") (pintype "output"))
    )
    (net (code "104") (name "unconnected-(DD2-CR-Pad20)") (class "Default")
      (node (ref "DD2") (pin "20") (pinfunction "CR_20") (pintype "passive"))
    )
    (net (code "105") (name "unconnected-(DD2-TEST-Pad4)") (class "Default")
      (node (ref "DD2") (pin "4") (pinfunction "TEST_4") (pintype "output"))
    )
    (net (code "106") (name "unconnected-(DD2-TEST-Pad18)") (class "Default")
      (node (ref "DD2") (pin "18") (pinfunction "TEST_18") (pintype "output"))
    )
    (net (code "107") (name "unconnected-(DD2-TMO-Pad23)") (class "Default")
      (node (ref "DD2") (pin "23") (pinfunction "TMO_23") (pintype "output"))
    )
    (net (code "108") (name "unconnected-(DD2-TRG-Pad22)") (class "Default")
      (node (ref "DD2") (pin "22") (pinfunction "TRG_22") (pintype "passive"))
    )
    (net (code "109") (name "unconnected-(DD4D-C-Pad11)") (class "Default")
      (node (ref "DD4") (pin "11") (pinfunction "C_11") (pintype "output"))
    )
    (net (code "110") (name "unconnected-(DD6-Y2-Pad13)") (class "Default")
      (node (ref "DD6") (pin "13") (pinfunction "Y2_13") (pintype "output"))
    )
    (net (code "111") (name "unconnected-(DD6-Y3-Pad12)") (class "Default")
      (node (ref "DD6") (pin "12") (pinfunction "Y3_12") (pintype "output"))
    )
    (net (code "112") (name "unconnected-(DD6-Y4-Pad11)") (class "Default")
      (node (ref "DD6") (pin "11") (pinfunction "Y4_11") (pintype "output"))
    )
    (net (code "113") (name "unconnected-(DD6-Y6-Pad9)") (class "Default")
      (node (ref "DD6") (pin "9") (pinfunction "Y6_9") (pintype "output"))
    )
    (net (code "114") (name "unconnected-(DD6-Y7-Pad7)") (class "Default")
      (node (ref "DD6") (pin "7") (pinfunction "Y7_7") (pintype "output"))
    )
    (net (code "115") (name "unconnected-(DD7-Q0-Pad2)") (class "Default")
      (node (ref "DD7") (pin "2") (pinfunction "Q0_2") (pintype "output"))
    )
    (net (code "116") (name "unconnected-(DD7-Q0{slash}-Pad3)") (class "Default")
      (node (ref "DD7") (pin "3") (pinfunction "Q0/_3") (pintype "output"))
    )
    (net (code "117") (name "unconnected-(DD7-Q1-Pad7)") (class "Default")
      (node (ref "DD7") (pin "7") (pinfunction "Q1_7") (pintype "output"))
    )
    (net (code "118") (name "unconnected-(DD7-Q1{slash}-Pad6)") (class "Default")
      (node (ref "DD7") (pin "6") (pinfunction "Q1/_6") (pintype "output"))
    )
    (net (code "119") (name "unconnected-(DD7-Q2-Pad10)") (class "Default")
      (node (ref "DD7") (pin "10") (pinfunction "Q2_10") (pintype "output"))
    )
    (net (code "120") (name "unconnected-(DD7-Q2{slash}-Pad11)") (class "Default")
      (node (ref "DD7") (pin "11") (pinfunction "Q2/_11") (pintype "output"))
    )
    (net (code "121") (name "unconnected-(DD7-Q4-Pad15)") (class "Default")
      (node (ref "DD7") (pin "15") (pinfunction "Q4_15") (pintype "output"))
    )
    (net (code "122") (name "unconnected-(XP1-A15-Pad15)") (class "Default")
      (node (ref "XP1") (pin "15") (pinfunction "A15_15") (pintype "passive"))
    )
    (net (code "123") (name "unconnected-(XP1-A16-Pad16)") (class "Default")
      (node (ref "XP1") (pin "16") (pinfunction "A16_16") (pintype "passive"))
    )
    (net (code "124") (name "unconnected-(XP1-A17-Pad17)") (class "Default")
      (node (ref "XP1") (pin "17") (pinfunction "A17_17") (pintype "passive"))
    )
    (net (code "125") (name "unconnected-(XP1-A18-Pad18)") (class "Default")
      (node (ref "XP1") (pin "18") (pinfunction "A18_18") (pintype "passive"))
    )
    (net (code "126") (name "unconnected-(XP1-B4-Pad32)") (class "Default")
      (node (ref "XP1") (pin "32") (pinfunction "B4_32") (pintype "passive"))
    )
    (net (code "127") (name "unconnected-(XP1-B28-Pad56)") (class "Default")
      (node (ref "XP1") (pin "56") (pinfunction "B28_56") (pintype "passive"))
    )
    (net (code "128") (name "unconnected-(XP2-A15-Pad15)") (class "Default")
      (node (ref "XP2") (pin "15") (pinfunction "A15_15") (pintype "passive"))
    )
    (net (code "129") (name "unconnected-(XP2-A16-Pad16)") (class "Default")
      (node (ref "XP2") (pin "16") (pinfunction "A16_16") (pintype "passive"))
    )
    (net (code "130") (name "unconnected-(XP2-A17-Pad17)") (class "Default")
      (node (ref "XP2") (pin "17") (pinfunction "A17_17") (pintype "passive"))
    )
    (net (code "131") (name "unconnected-(XP2-A18-Pad18)") (class "Default")
      (node (ref "XP2") (pin "18") (pinfunction "A18_18") (pintype "passive"))
    )
    (net (code "132") (name "unconnected-(XP2-B4-Pad32)") (class "Default")
      (node (ref "XP2") (pin "32") (pinfunction "B4_32") (pintype "passive"))
    )
    (net (code "133") (name "unconnected-(XP2-B28-Pad56)") (class "Default")
      (node (ref "XP2") (pin "56") (pinfunction "B28_56") (pintype "passive"))
    )
    (net (code "134") (name "unconnected-(XP3-Pad4)") (class "Default")
      (node (ref "XP3") (pin "4") (pintype "passive"))
    )
    (net (code "135") (name "unconnected-(XP4-Pad26)") (class "Default")
      (node (ref "XP4") (pin "26") (pintype "passive"))
    )
    (net (code "136") (name "unconnected-(XP4-Pad27)") (class "Default")
      (node (ref "XP4") (pin "27") (pintype "passive"))
    )
    (net (code "137") (name "unconnected-(XP4-Pad28)") (class "Default")
      (node (ref "XP4") (pin "28") (pintype "passive"))
    )
    (net (code "138") (name "unconnected-(XP4-Pad29)") (class "Default")
      (node (ref "XP4") (pin "29") (pintype "passive"))
    )
    (net (code "139") (name "unconnected-(XP4-Pad30)") (class "Default")
      (node (ref "XP4") (pin "30") (pintype "passive"))
    )
    (net (code "140") (name "unconnected-(XP4-Pad31)") (class "Default")
      (node (ref "XP4") (pin "31") (pintype "passive"))
    )
    (net (code "141") (name "unconnected-(XP4-Pad32)") (class "Default")
      (node (ref "XP4") (pin "32") (pintype "passive"))
    )
    (net (code "142") (name "unconnected-(XP4-Pad33)") (class "Default")
      (node (ref "XP4") (pin "33") (pintype "passive"))
    )
    (net (code "143") (name "unconnected-(XP4-Pad34)") (class "Default")
      (node (ref "XP4") (pin "34") (pintype "passive"))
    )
    (net (code "144") (name "unconnected-(XP4-Pad35)") (class "Default")
      (node (ref "XP4") (pin "35") (pintype "passive"))
    )
    (net (code "145") (name "unconnected-(XP4-Pad36)") (class "Default")
      (node (ref "XP4") (pin "36") (pintype "passive"))
    )
    (net (code "146") (name "unconnected-(XP4-Pad37)") (class "Default")
      (node (ref "XP4") (pin "37") (pintype "passive"))
    )
    (net (code "147") (name "unconnected-(XP4-Pad38)") (class "Default")
      (node (ref "XP4") (pin "38") (pintype "passive"))
    )
    (net (code "148") (name "unconnected-(XP4-Pad39)") (class "Default")
      (node (ref "XP4") (pin "39") (pintype "passive"))
    )
    (net (code "149") (name "unconnected-(XP4-Pad40)") (class "Default")
      (node (ref "XP4") (pin "40") (pintype "passive"))
    )
    (net (code "150") (name "unconnected-(XP4-Pad41)") (class "Default")
      (node (ref "XP4") (pin "41") (pintype "passive"))
    )
    (net (code "151") (name "unconnected-(XP4-Pad42)") (class "Default")
      (node (ref "XP4") (pin "42") (pintype "passive"))
    )
    (net (code "152") (name "unconnected-(XP4-Pad43)") (class "Default")
      (node (ref "XP4") (pin "43") (pintype "passive"))
    )
    (net (code "153") (name "unconnected-(XP4-Pad44)") (class "Default")
      (node (ref "XP4") (pin "44") (pintype "passive"))
    )
    (net (code "154") (name "unconnected-(XP4-Pad45)") (class "Default")
      (node (ref "XP4") (pin "45") (pintype "passive"))
    )
    (net (code "155") (name "unconnected-(XP4-Pad46)") (class "Default")
      (node (ref "XP4") (pin "46") (pintype "passive"))
    )
    (net (code "156") (name "unconnected-(XP4-Pad47)") (class "Default")
      (node (ref "XP4") (pin "47") (pintype "passive"))
    )
    (net (code "157") (name "unconnected-(XP4-Pad48)") (class "Default")
      (node (ref "XP4") (pin "48") (pintype "passive"))
    )
    (net (code "158") (name "unconnected-(XP4-Pad49)") (class "Default")
      (node (ref "XP4") (pin "49") (pintype "passive"))
    )
    (net (code "159") (name "unconnected-(XP4-Pad50)") (class "Default")
      (node (ref "XP4") (pin "50") (pintype "passive"))
    )
  )
)
